# LoRa_ST_Sensor_Node_v2_0.net
KiCad netlist of a schematic drawn in EAGLE
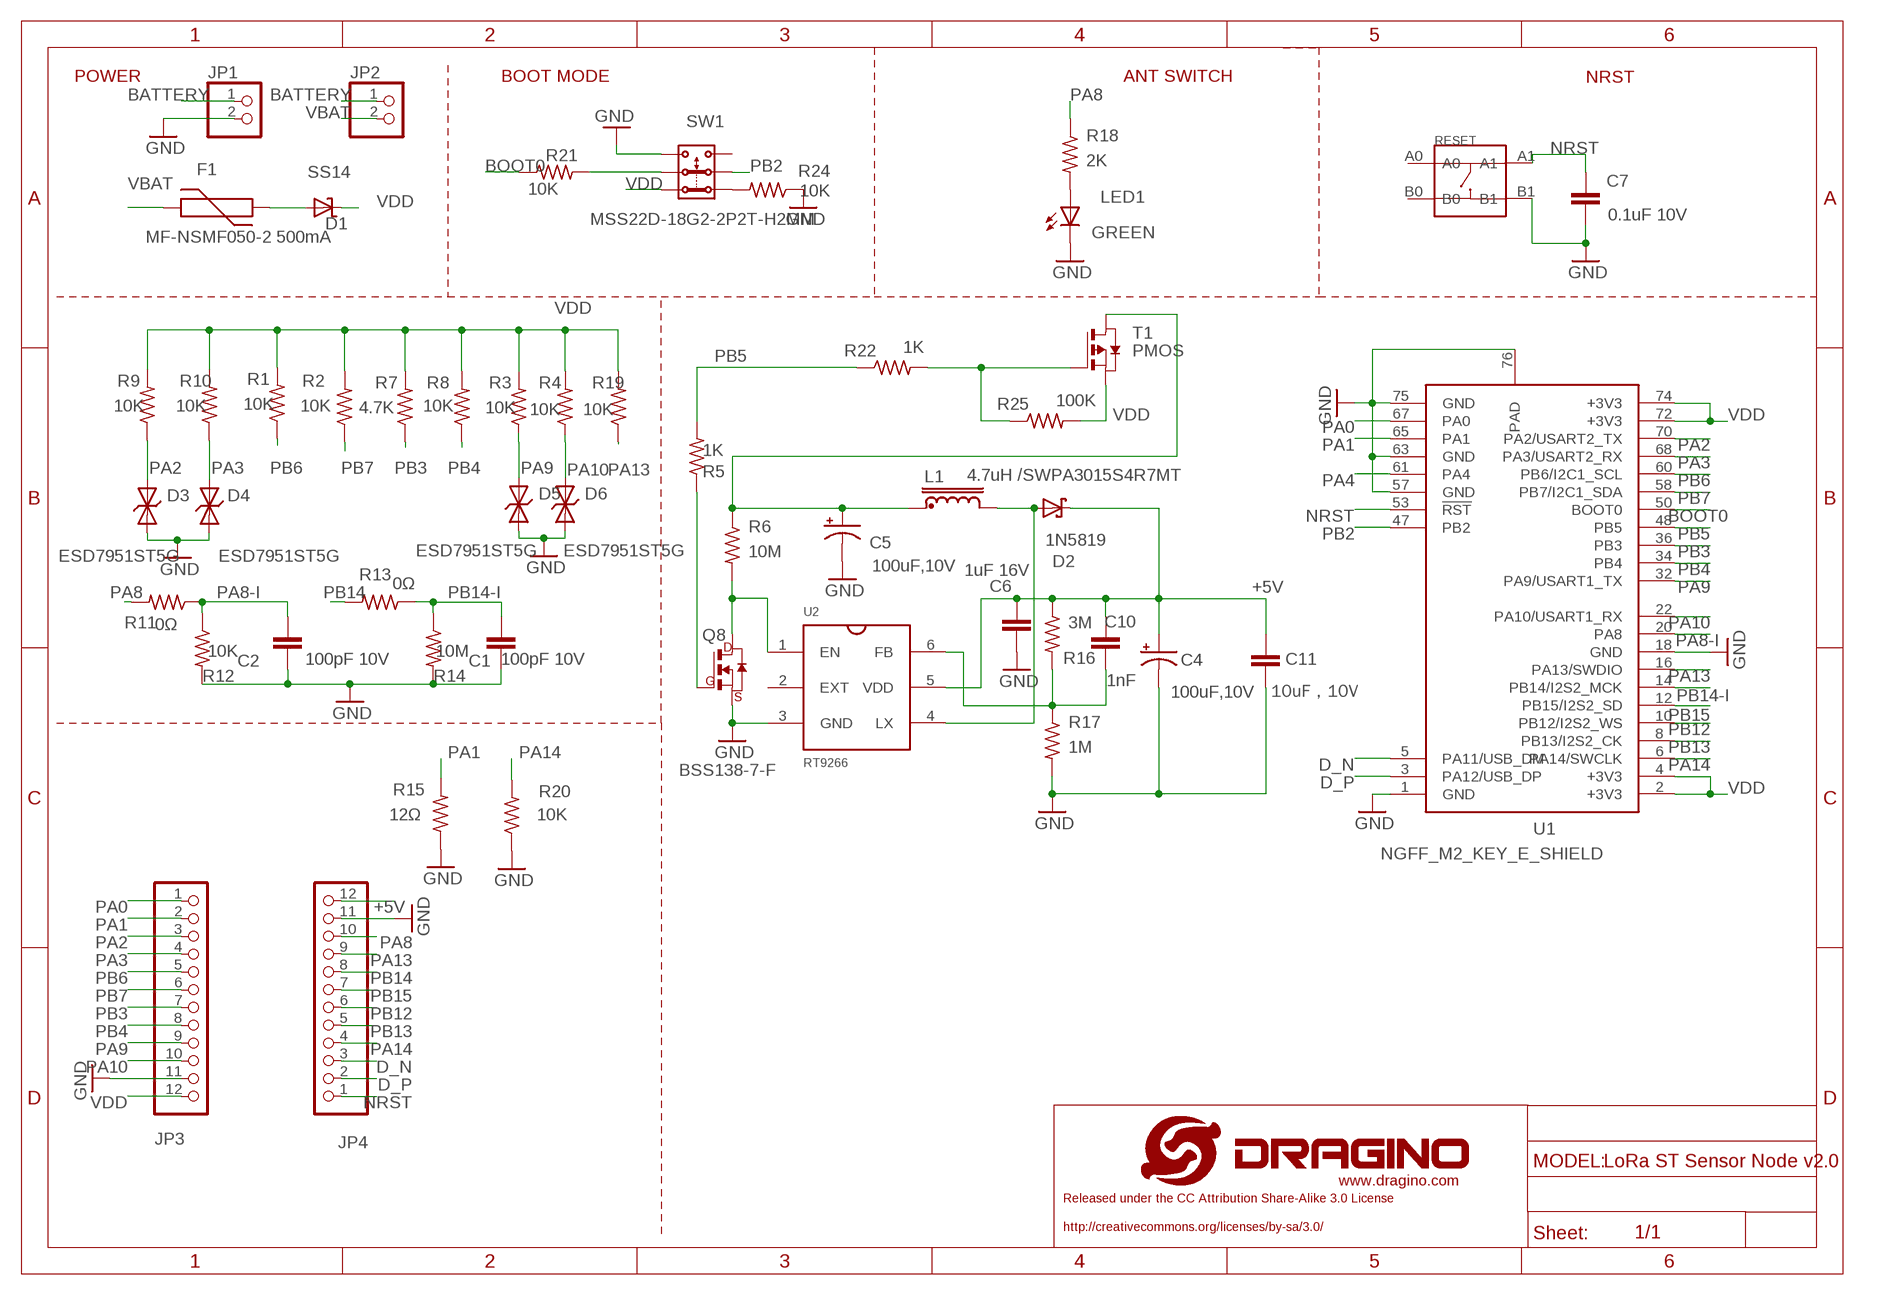
[diagram p0: schematic, sheet 1]

(export (version "E")
  (design (tool "Eeschema 10.0.6"))
  (components
    (comp (ref "C1")
      (value "100pF 10V")
      (footprint "eagle-import:C0603")
      (libsource (lib "eagle-import") (part "C-EUC0603"))
    )
    (comp (ref "C2")
      (value "100pF 10V")
      (footprint "eagle-import:C0603")
      (libsource (lib "eagle-import") (part "C-EUC0603"))
    )
    (comp (ref "C4")
      (value "100uF,10V")
      (footprint "eagle-import:SMC_B")
      (libsource (lib "eagle-import") (part "CPOL-USSMCB"))
    )
    (comp (ref "C5")
      (value "100uF,10V")
      (footprint "eagle-import:SMC_B")
      (libsource (lib "eagle-import") (part "CPOL-USSMCB"))
    )
    (comp (ref "C6")
      (value "1uF 16V")
      (footprint "eagle-import:C0603")
      (libsource (lib "eagle-import") (part "C-EUC0603"))
    )
    (comp (ref "C7")
      (value "0.1uF 10V")
      (footprint "eagle-import:C0402")
      (libsource (lib "eagle-import") (part "C-EUC0402"))
    )
    (comp (ref "C10")
      (value "1nF")
      (footprint "eagle-import:C0402")
      (libsource (lib "eagle-import") (part "C-EUC0402"))
    )
    (comp (ref "C11")
      (value "10uF，10V")
      (footprint "eagle-import:C0805")
      (libsource (lib "eagle-import") (part "dragino-passive_C-EUC0805"))
    )
    (comp (ref "D1")
      (value "SS14")
      (footprint "eagle-import:DO214AC")
      (libsource (lib "eagle-import") (part "SCHOTTKYSMBG"))
    )
    (comp (ref "D2")
      (value "1N5819")
      (footprint "eagle-import:SOD123FL")
      (libsource (lib "eagle-import") (part "SMF5.0AT1"))
    )
    (comp (ref "D3")
      (value "ESD7951ST5G")
      (footprint "eagle-import:SOD−923")
      (libsource (lib "eagle-import") (part "TVSSOD−923"))
    )
    (comp (ref "D4")
      (value "ESD7951ST5G")
      (footprint "eagle-import:SOD−923")
      (libsource (lib "eagle-import") (part "TVSSOD−923"))
    )
    (comp (ref "D5")
      (value "ESD7951ST5G")
      (footprint "eagle-import:SOD−923")
      (libsource (lib "eagle-import") (part "TVSSOD−923"))
    )
    (comp (ref "D6")
      (value "ESD7951ST5G")
      (footprint "eagle-import:SOD−923")
      (libsource (lib "eagle-import") (part "TVSSOD−923"))
    )
    (comp (ref "F1")
      (value "MF-NSMF050-2 500mA")
      (footprint "eagle-import:R1206")
      (libsource (lib "eagle-import") (part "FUSE1206"))
    )
    (comp (ref "JP1")
      (value "PINHD-1X2L")
      (footprint "eagle-import:XH2.54-2P-L")
      (libsource (lib "eagle-import") (part "PINHD-1X2L"))
    )
    (comp (ref "JP2")
      (value "PINHD-1X2")
      (footprint "eagle-import:1X02")
      (libsource (lib "eagle-import") (part "PINHD-1X2"))
    )
    (comp (ref "JP3")
      (value "PINHD-1X12\"\"")
      (footprint "eagle-import:1X12-DIP")
      (libsource (lib "eagle-import") (part "PINHD-1X12{dblquote}{dblquote}"))
    )
    (comp (ref "JP4")
      (value "PINHD-1X12\"\"")
      (footprint "eagle-import:1X12-DIP")
      (libsource (lib "eagle-import") (part "PINHD-1X12{dblquote}{dblquote}"))
    )
    (comp (ref "L1")
      (value "4.7uH /SWPA3015S4R7MT")
      (footprint "eagle-import:SWPA3010S")
      (libsource (lib "eagle-import") (part "INDUCTORSWPA3010S"))
    )
    (comp (ref "LED1")
      (value "GREEN")
      (footprint "eagle-import:CHIPLED_0603")
      (libsource (lib "eagle-import") (part "LEDCHIPLED_0603"))
    )
    (comp (ref "Q8")
      (value "BSS138-7-F")
      (footprint "eagle-import:SOT-23")
      (libsource (lib "eagle-import") (part "NMOSFET"))
    )
    (comp (ref "R1")
      (value "10K")
      (footprint "eagle-import:R0402")
      (libsource (lib "eagle-import") (part "R-US_R0402"))
    )
    (comp (ref "R2")
      (value "10K")
      (footprint "eagle-import:R0402")
      (libsource (lib "eagle-import") (part "R-US_R0402"))
    )
    (comp (ref "R3")
      (value "10K")
      (footprint "eagle-import:R0402")
      (libsource (lib "eagle-import") (part "R-US_R0402"))
    )
    (comp (ref "R4")
      (value "10K")
      (footprint "eagle-import:R0402")
      (libsource (lib "eagle-import") (part "R-US_R0402"))
    )
    (comp (ref "R5")
      (value "1K")
      (footprint "eagle-import:R0402")
      (libsource (lib "eagle-import") (part "R-US_R0402"))
    )
    (comp (ref "R6")
      (value "10M")
      (footprint "eagle-import:R0402")
      (libsource (lib "eagle-import") (part "R-US_R0402"))
    )
    (comp (ref "R7")
      (value "4.7K")
      (footprint "eagle-import:R0402")
      (libsource (lib "eagle-import") (part "R-US_R0402"))
    )
    (comp (ref "R8")
      (value "10K")
      (footprint "eagle-import:R0402")
      (libsource (lib "eagle-import") (part "R-US_R0402"))
    )
    (comp (ref "R9")
      (value "10K")
      (footprint "eagle-import:R0402")
      (libsource (lib "eagle-import") (part "R-US_R0402"))
    )
    (comp (ref "R10")
      (value "10K")
      (footprint "eagle-import:R0402")
      (libsource (lib "eagle-import") (part "R-US_R0402"))
    )
    (comp (ref "R11")
      (value "0Ω")
      (footprint "eagle-import:R0603")
      (libsource (lib "eagle-import") (part "R-US_R0603"))
    )
    (comp (ref "R12")
      (value "10K")
      (footprint "eagle-import:R0603")
      (libsource (lib "eagle-import") (part "R-US_R0603"))
    )
    (comp (ref "R13")
      (value "0Ω")
      (footprint "eagle-import:R0603")
      (libsource (lib "eagle-import") (part "R-US_R0603"))
    )
    (comp (ref "R14")
      (value "10M")
      (footprint "eagle-import:R0603")
      (libsource (lib "eagle-import") (part "R-US_R0603"))
    )
    (comp (ref "R15")
      (value "12Ω")
      (footprint "eagle-import:R1206@1")
      (libsource (lib "eagle-import") (part "R-US_R1206"))
    )
    (comp (ref "R16")
      (value "3M")
      (footprint "eagle-import:R0402")
      (libsource (lib "eagle-import") (part "R-US_R0402"))
    )
    (comp (ref "R17")
      (value "1M")
      (footprint "eagle-import:R0402")
      (libsource (lib "eagle-import") (part "R-US_R0402"))
    )
    (comp (ref "R18")
      (value "2K")
      (footprint "eagle-import:R0402")
      (libsource (lib "eagle-import") (part "R-US_R0402"))
    )
    (comp (ref "R19")
      (value "10K")
      (footprint "eagle-import:R0402")
      (libsource (lib "eagle-import") (part "R-US_R0402"))
    )
    (comp (ref "R20")
      (value "10K")
      (footprint "eagle-import:R0402")
      (libsource (lib "eagle-import") (part "R-US_R0402"))
    )
    (comp (ref "R21")
      (value "10K")
      (footprint "eagle-import:R0402")
      (libsource (lib "eagle-import") (part "R-US_R0402"))
    )
    (comp (ref "R22")
      (value "1K")
      (footprint "eagle-import:R0402")
      (libsource (lib "eagle-import") (part "R-US_R0402"))
    )
    (comp (ref "R24")
      (value "10K")
      (footprint "eagle-import:R0402")
      (libsource (lib "eagle-import") (part "R-US_R0402"))
    )
    (comp (ref "R25")
      (value "100K")
      (footprint "eagle-import:R0402")
      (libsource (lib "eagle-import") (part "R-US_R0402"))
    )
    (comp (ref "RESET")
      (value "轻触开关3*3*1.5四脚贴片开关")
      (footprint "eagle-import:SW4-SMD-3.35X3.35X1.5MM")
      (libsource (lib "eagle-import") (part "BUTTON-4P-3.3X3.3"))
    )
    (comp (ref "SW1")
      (value "MSS22D-18G2-2P2T-H2MM")
      (footprint "eagle-import:MSS22D-18G2-2P2T-H2MM-DIL")
      (libsource (lib "eagle-import") (part "MSS22D-18G2-2P2T-H2MM"))
    )
    (comp (ref "T1")
      (value "PMOS")
      (footprint "eagle-import:SOT-23")
      (libsource (lib "eagle-import") (part "PMOSSOT23"))
    )
    (comp (ref "U1")
      (value "NGFF_M2_KEY_E_SHIELD")
      (footprint "eagle-import:NGFF_M2_KEY_E_SHIELD")
      (libsource (lib "eagle-import") (part "NGFF_M2_KEY_E_SHIELD"))
    )
    (comp (ref "U2")
      (value "RT9266")
      (footprint "eagle-import:6_SOT-23")
      (libsource (lib "eagle-import") (part "RT9266"))
    )
  )
  (nets
    (net (code "1") (name "/+5V") (class "Default")
      (node (ref "C10") (pin "2") (pinfunction "2_2") (pintype "passive"))
      (node (ref "C11") (pin "2") (pinfunction "2_2") (pintype "passive"))
      (node (ref "C4") (pin "+") (pinfunction "+_+") (pintype "passive"))
      (node (ref "C6") (pin "2") (pinfunction "2_2") (pintype "passive"))
      (node (ref "D2") (pin "C") (pinfunction "C_C") (pintype "passive"))
      (node (ref "JP4") (pin "12") (pinfunction "12_12") (pintype "passive"))
      (node (ref "R16") (pin "1") (pinfunction "1_1") (pintype "passive"))
      (node (ref "U2") (pin "5") (pinfunction "VDD_5") (pintype "bidirectional"))
    )
    (net (code "2") (name "/BATTERY") (class "Default")
      (node (ref "JP1") (pin "1") (pinfunction "1_1") (pintype "passive"))
      (node (ref "JP2") (pin "1") (pinfunction "1_1") (pintype "passive"))
    )
    (net (code "3") (name "/BOOT0") (class "Default")
      (node (ref "R21") (pin "1") (pinfunction "1_1") (pintype "passive"))
      (node (ref "U1") (pin "50") (pinfunction "BOOT0_50") (pintype "bidirectional"))
    )
    (net (code "4") (name "/D_N") (class "Default")
      (node (ref "JP4") (pin "3") (pinfunction "3_3") (pintype "passive"))
      (node (ref "U1") (pin "5") (pinfunction "PA11/USB_DM_5") (pintype "bidirectional"))
    )
    (net (code "5") (name "/D_P") (class "Default")
      (node (ref "JP4") (pin "2") (pinfunction "2_2") (pintype "passive"))
      (node (ref "U1") (pin "3") (pinfunction "PA12/USB_DP_3") (pintype "bidirectional"))
    )
    (net (code "6") (name "/NRST") (class "Default")
      (node (ref "C7") (pin "2") (pinfunction "2_2") (pintype "passive"))
      (node (ref "JP4") (pin "1") (pinfunction "1_1") (pintype "passive"))
      (node (ref "RESET") (pin "A1") (pinfunction "A1_A1") (pintype "bidirectional"))
      (node (ref "U1") (pin "53") (pinfunction "~{RST}_53") (pintype "bidirectional"))
    )
    (net (code "7") (name "/PA0") (class "Default")
      (node (ref "JP3") (pin "1") (pinfunction "1_1") (pintype "passive"))
      (node (ref "U1") (pin "67") (pinfunction "PA0_67") (pintype "bidirectional"))
    )
    (net (code "8") (name "/PA1") (class "Default")
      (node (ref "JP3") (pin "2") (pinfunction "2_2") (pintype "passive"))
      (node (ref "R15") (pin "2") (pinfunction "2_2") (pintype "passive"))
      (node (ref "U1") (pin "65") (pinfunction "PA1_65") (pintype "bidirectional"))
    )
    (net (code "9") (name "/PA2") (class "Default")
      (node (ref "D3") (pin "P$1") (pinfunction "1_P$1") (pintype "passive"))
      (node (ref "JP3") (pin "3") (pinfunction "3_3") (pintype "passive"))
      (node (ref "R9") (pin "1") (pinfunction "1_1") (pintype "passive"))
      (node (ref "U1") (pin "70") (pinfunction "PA2/USART2_TX_70") (pintype "bidirectional"))
    )
    (net (code "10") (name "/PA3") (class "Default")
      (node (ref "D4") (pin "P$1") (pinfunction "1_P$1") (pintype "passive"))
      (node (ref "JP3") (pin "4") (pinfunction "4_4") (pintype "passive"))
      (node (ref "R10") (pin "1") (pinfunction "1_1") (pintype "passive"))
      (node (ref "U1") (pin "68") (pinfunction "PA3/USART2_RX_68") (pintype "bidirectional"))
    )
    (net (code "11") (name "/PA4") (class "Default")
      (node (ref "U1") (pin "61") (pinfunction "PA4_61") (pintype "bidirectional"))
    )
    (net (code "12") (name "/PA8") (class "Default")
      (node (ref "JP4") (pin "10") (pinfunction "10_10") (pintype "passive"))
      (node (ref "R11") (pin "2") (pinfunction "2_2") (pintype "passive"))
      (node (ref "R18") (pin "1") (pinfunction "1_1") (pintype "passive"))
    )
    (net (code "13") (name "/PA8-I") (class "Default")
      (node (ref "C2") (pin "2") (pinfunction "2_2") (pintype "passive"))
      (node (ref "R11") (pin "1") (pinfunction "1_1") (pintype "passive"))
      (node (ref "R12") (pin "1") (pinfunction "1_1") (pintype "passive"))
      (node (ref "U1") (pin "20") (pinfunction "PA8_20") (pintype "bidirectional"))
    )
    (net (code "14") (name "/PA9") (class "Default")
      (node (ref "D5") (pin "P$1") (pinfunction "1_P$1") (pintype "passive"))
      (node (ref "JP3") (pin "9") (pinfunction "9_9") (pintype "passive"))
      (node (ref "R3") (pin "1") (pinfunction "1_1") (pintype "passive"))
      (node (ref "U1") (pin "32") (pinfunction "PA9/USART1_TX_32") (pintype "bidirectional"))
    )
    (net (code "15") (name "/PA10") (class "Default")
      (node (ref "D6") (pin "P$1") (pinfunction "1_P$1") (pintype "passive"))
      (node (ref "JP3") (pin "10") (pinfunction "10_10") (pintype "passive"))
      (node (ref "R4") (pin "1") (pinfunction "1_1") (pintype "passive"))
      (node (ref "U1") (pin "22") (pinfunction "PA10/USART1_RX_22") (pintype "bidirectional"))
    )
    (net (code "16") (name "/PA13") (class "Default")
      (node (ref "JP4") (pin "9") (pinfunction "9_9") (pintype "passive"))
      (node (ref "R19") (pin "1") (pinfunction "1_1") (pintype "passive"))
      (node (ref "U1") (pin "16") (pinfunction "PA13/SWDIO_16") (pintype "bidirectional"))
    )
    (net (code "17") (name "/PA14") (class "Default")
      (node (ref "JP4") (pin "4") (pinfunction "4_4") (pintype "passive"))
      (node (ref "R20") (pin "2") (pinfunction "2_2") (pintype "passive"))
      (node (ref "U1") (pin "6") (pinfunction "PA14/SWCLK_6") (pintype "bidirectional"))
    )
    (net (code "18") (name "/PB2") (class "Default")
      (node (ref "SW1") (pin "5") (pinfunction "5_5") (pintype "bidirectional"))
      (node (ref "U1") (pin "47") (pinfunction "PB2_47") (pintype "bidirectional"))
    )
    (net (code "19") (name "/PB3") (class "Default")
      (node (ref "JP3") (pin "7") (pinfunction "7_7") (pintype "passive"))
      (node (ref "R7") (pin "1") (pinfunction "1_1") (pintype "passive"))
      (node (ref "U1") (pin "36") (pinfunction "PB3_36") (pintype "bidirectional"))
    )
    (net (code "20") (name "/PB4") (class "Default")
      (node (ref "JP3") (pin "8") (pinfunction "8_8") (pintype "passive"))
      (node (ref "R8") (pin "1") (pinfunction "1_1") (pintype "passive"))
      (node (ref "U1") (pin "34") (pinfunction "PB4_34") (pintype "bidirectional"))
    )
    (net (code "21") (name "/PB5") (class "Default")
      (node (ref "R22") (pin "1") (pinfunction "1_1") (pintype "passive"))
      (node (ref "R5") (pin "2") (pinfunction "2_2") (pintype "passive"))
      (node (ref "U1") (pin "48") (pinfunction "PB5_48") (pintype "bidirectional"))
    )
    (net (code "22") (name "/PB6") (class "Default")
      (node (ref "JP3") (pin "5") (pinfunction "5_5") (pintype "passive"))
      (node (ref "R1") (pin "1") (pinfunction "1_1") (pintype "passive"))
      (node (ref "U1") (pin "60") (pinfunction "PB6/I2C1_SCL_60") (pintype "bidirectional"))
    )
    (net (code "23") (name "/PB7") (class "Default")
      (node (ref "JP3") (pin "6") (pinfunction "6_6") (pintype "passive"))
      (node (ref "R2") (pin "1") (pinfunction "1_1") (pintype "passive"))
      (node (ref "U1") (pin "58") (pinfunction "PB7/I2C1_SDA_58") (pintype "bidirectional"))
    )
    (net (code "24") (name "/PB12") (class "Default")
      (node (ref "JP4") (pin "6") (pinfunction "6_6") (pintype "passive"))
      (node (ref "U1") (pin "10") (pinfunction "PB12/I2S2_WS_10") (pintype "bidirectional"))
    )
    (net (code "25") (name "/PB13") (class "Default")
      (node (ref "JP4") (pin "5") (pinfunction "5_5") (pintype "passive"))
      (node (ref "U1") (pin "8") (pinfunction "PB13/I2S2_CK_8") (pintype "bidirectional"))
    )
    (net (code "26") (name "/PB14") (class "Default")
      (node (ref "JP4") (pin "8") (pinfunction "8_8") (pintype "passive"))
      (node (ref "R13") (pin "2") (pinfunction "2_2") (pintype "passive"))
    )
    (net (code "27") (name "/PB14-I") (class "Default")
      (node (ref "C1") (pin "2") (pinfunction "2_2") (pintype "passive"))
      (node (ref "R13") (pin "1") (pinfunction "1_1") (pintype "passive"))
      (node (ref "R14") (pin "1") (pinfunction "1_1") (pintype "passive"))
      (node (ref "U1") (pin "14") (pinfunction "PB14/I2S2_MCK_14") (pintype "bidirectional"))
    )
    (net (code "28") (name "/PB15") (class "Default")
      (node (ref "JP4") (pin "7") (pinfunction "7_7") (pintype "passive"))
      (node (ref "U1") (pin "12") (pinfunction "PB15/I2S2_SD_12") (pintype "bidirectional"))
    )
    (net (code "29") (name "/VBAT") (class "Default")
      (node (ref "F1") (pin "2") (pinfunction "2_2") (pintype "passive"))
      (node (ref "JP2") (pin "2") (pinfunction "2_2") (pintype "passive"))
    )
    (net (code "30") (name "/VDD") (class "Default")
      (node (ref "D1") (pin "C") (pinfunction "C_C") (pintype "passive"))
      (node (ref "JP3") (pin "12") (pinfunction "12_12") (pintype "passive"))
      (node (ref "R1") (pin "2") (pinfunction "2_2") (pintype "passive"))
      (node (ref "R10") (pin "2") (pinfunction "2_2") (pintype "passive"))
      (node (ref "R19") (pin "2") (pinfunction "2_2") (pintype "passive"))
      (node (ref "R2") (pin "2") (pinfunction "2_2") (pintype "passive"))
      (node (ref "R25") (pin "2") (pinfunction "2_2") (pintype "passive"))
      (node (ref "R3") (pin "2") (pinfunction "2_2") (pintype "passive"))
      (node (ref "R4") (pin "2") (pinfunction "2_2") (pintype "passive"))
      (node (ref "R7") (pin "2") (pinfunction "2_2") (pintype "passive"))
      (node (ref "R8") (pin "2") (pinfunction "2_2") (pintype "passive"))
      (node (ref "R9") (pin "2") (pinfunction "2_2") (pintype "passive"))
      (node (ref "SW1") (pin "3") (pinfunction "3_3") (pintype "bidirectional"))
      (node (ref "T1") (pin "2") (pinfunction "S_2") (pintype "passive"))
      (node (ref "U1") (pin "2") (pinfunction "+3V3_2") (pintype "bidirectional"))
      (node (ref "U1") (pin "4") (pinfunction "+3V3_4") (pintype "bidirectional"))
      (node (ref "U1") (pin "72") (pinfunction "+3V3_72") (pintype "bidirectional"))
      (node (ref "U1") (pin "74") (pinfunction "+3V3_74") (pintype "bidirectional"))
    )
    (net (code "31") (name "GND") (class "Default")
      (node (ref "C1") (pin "1") (pinfunction "1_1") (pintype "passive"))
      (node (ref "C11") (pin "1") (pinfunction "1_1") (pintype "passive"))
      (node (ref "C2") (pin "1") (pinfunction "1_1") (pintype "passive"))
      (node (ref "C4") (pin "-") (pinfunction "-_-") (pintype "passive"))
      (node (ref "C5") (pin "-") (pinfunction "-_-") (pintype "passive"))
      (node (ref "C6") (pin "1") (pinfunction "1_1") (pintype "passive"))
      (node (ref "C7") (pin "1") (pinfunction "1_1") (pintype "passive"))
      (node (ref "D3") (pin "P$2") (pinfunction "2_P$2") (pintype "passive"))
      (node (ref "D4") (pin "P$2") (pinfunction "2_P$2") (pintype "passive"))
      (node (ref "D5") (pin "P$2") (pinfunction "2_P$2") (pintype "passive"))
      (node (ref "D6") (pin "P$2") (pinfunction "2_P$2") (pintype "passive"))
      (node (ref "JP1") (pin "2") (pinfunction "2_2") (pintype "passive"))
      (node (ref "JP3") (pin "11") (pinfunction "11_11") (pintype "passive"))
      (node (ref "JP4") (pin "11") (pinfunction "11_11") (pintype "passive"))
      (node (ref "LED1") (pin "C") (pinfunction "C_C") (pintype "passive"))
      (node (ref "Q8") (pin "2") (pinfunction "S_2") (pintype "passive"))
      (node (ref "R12") (pin "2") (pinfunction "2_2") (pintype "passive"))
      (node (ref "R14") (pin "2") (pinfunction "2_2") (pintype "passive"))
      (node (ref "R15") (pin "1") (pinfunction "1_1") (pintype "passive"))
      (node (ref "R17") (pin "2") (pinfunction "2_2") (pintype "passive"))
      (node (ref "R20") (pin "1") (pinfunction "1_1") (pintype "passive"))
      (node (ref "R24") (pin "1") (pinfunction "1_1") (pintype "passive"))
      (node (ref "RESET") (pin "B1") (pinfunction "B1_B1") (pintype "bidirectional"))
      (node (ref "SW1") (pin "1") (pinfunction "1_1") (pintype "bidirectional"))
      (node (ref "U1") (pin "1") (pinfunction "GND_1") (pintype "bidirectional"))
      (node (ref "U1") (pin "18") (pinfunction "GND_18") (pintype "bidirectional"))
      (node (ref "U1") (pin "57") (pinfunction "GND_57") (pintype "bidirectional"))
      (node (ref "U1") (pin "63") (pinfunction "GND_63") (pintype "bidirectional"))
      (node (ref "U1") (pin "75") (pinfunction "GND_75") (pintype "bidirectional"))
      (node (ref "U1") (pin "76") (pinfunction "PAD_76") (pintype "bidirectional"))
      (node (ref "U2") (pin "3") (pinfunction "GND_3") (pintype "bidirectional"))
    )
    (net (code "32") (name "Net-(D1-PadA)") (class "Default")
      (node (ref "D1") (pin "A") (pinfunction "A_A") (pintype "passive"))
      (node (ref "F1") (pin "1") (pinfunction "1_1") (pintype "passive"))
    )
    (net (code "33") (name "Net-(L1-1)") (class "Default")
      (node (ref "C5") (pin "+") (pinfunction "+_+") (pintype "passive"))
      (node (ref "L1") (pin "P$1") (pinfunction "1_P$1") (pintype "passive"))
      (node (ref "R6") (pin "1") (pinfunction "1_1") (pintype "passive"))
      (node (ref "T1") (pin "1") (pinfunction "D_1") (pintype "passive"))
    )
    (net (code "34") (name "Net-(L1-4)") (class "Default")
      (node (ref "D2") (pin "A") (pinfunction "A_A") (pintype "passive"))
      (node (ref "L1") (pin "P$2") (pinfunction "4_P$2") (pintype "passive"))
      (node (ref "U2") (pin "4") (pinfunction "LX_4") (pintype "bidirectional"))
    )
    (net (code "35") (name "Net-(LED1-PadA)") (class "Default")
      (node (ref "LED1") (pin "A") (pinfunction "A_A") (pintype "passive"))
      (node (ref "R18") (pin "2") (pinfunction "2_2") (pintype "passive"))
    )
    (net (code "36") (name "Net-(Q8-D)") (class "Default")
      (node (ref "Q8") (pin "1") (pinfunction "D_1") (pintype "passive"))
      (node (ref "R6") (pin "2") (pinfunction "2_2") (pintype "passive"))
      (node (ref "U2") (pin "1") (pinfunction "EN_1") (pintype "input"))
    )
    (net (code "37") (name "Net-(Q8-G)") (class "Default")
      (node (ref "Q8") (pin "3") (pinfunction "G_3") (pintype "passive"))
      (node (ref "R5") (pin "1") (pinfunction "1_1") (pintype "passive"))
    )
    (net (code "38") (name "Net-(R21-Pad2)") (class "Default")
      (node (ref "R21") (pin "2") (pinfunction "2_2") (pintype "passive"))
      (node (ref "SW1") (pin "2") (pinfunction "2_2") (pintype "bidirectional"))
    )
    (net (code "39") (name "Net-(R24-Pad2)") (class "Default")
      (node (ref "R24") (pin "2") (pinfunction "2_2") (pintype "passive"))
      (node (ref "SW1") (pin "4") (pinfunction "4_4") (pintype "bidirectional"))
    )
    (net (code "40") (name "Net-(T1-G)") (class "Default")
      (node (ref "R22") (pin "2") (pinfunction "2_2") (pintype "passive"))
      (node (ref "R25") (pin "1") (pinfunction "1_1") (pintype "passive"))
      (node (ref "T1") (pin "3") (pinfunction "G_3") (pintype "passive"))
    )
    (net (code "41") (name "Net-(U2-FB)") (class "Default")
      (node (ref "C10") (pin "1") (pinfunction "1_1") (pintype "passive"))
      (node (ref "R16") (pin "2") (pinfunction "2_2") (pintype "passive"))
      (node (ref "R17") (pin "1") (pinfunction "1_1") (pintype "passive"))
      (node (ref "U2") (pin "6") (pinfunction "FB_6") (pintype "bidirectional"))
    )
    (net (code "42") (name "unconnected-(RESET-PadA0)") (class "Default")
      (node (ref "RESET") (pin "A0") (pinfunction "A0_A0") (pintype "bidirectional"))
    )
    (net (code "43") (name "unconnected-(RESET-PadB0)") (class "Default")
      (node (ref "RESET") (pin "B0") (pinfunction "B0_B0") (pintype "bidirectional"))
    )
    (net (code "44") (name "unconnected-(SW1-Pad6)") (class "Default")
      (node (ref "SW1") (pin "6") (pinfunction "6_6") (pintype "bidirectional"))
    )
    (net (code "45") (name "unconnected-(U2-EXT-Pad2)") (class "Default")
      (node (ref "U2") (pin "2") (pinfunction "EXT_2") (pintype "bidirectional"))
    )
  )
)
